# mcu.net
KiCad netlist of a schematic drawn in Altium Designer
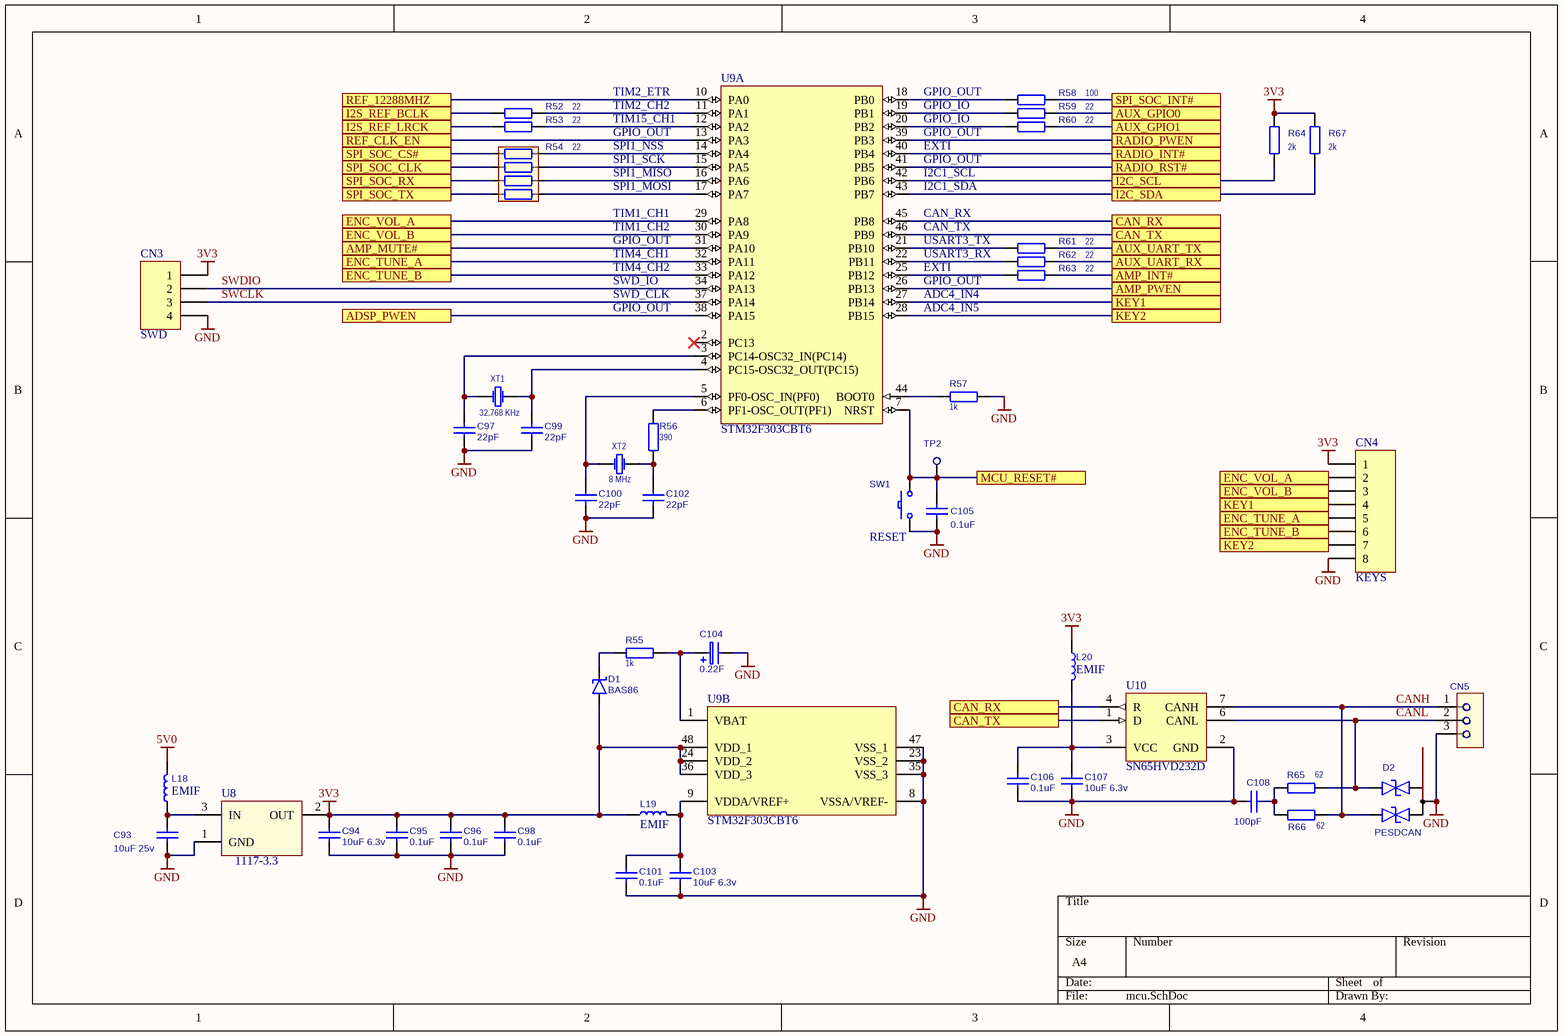
[diagram p0: mcu.SchDoc]

(export (version "E")
  (design (tool "Eeschema 10.0.6"))
  (components
    (comp (ref "C93")
      (value "10uF 25v")
      (footprint "C0805")
      (description "CAP_NPOL")
      (fields (field (name "Comment") "GRM21BR61E106KA73L"))
      (libsource (lib "capacitors") (part "CAP_NPOL"))
    )
    (comp (ref "C94")
      (value "10uF 6.3v")
      (footprint "Capacitors:C0603")
      (description "CAP_NPOL")
      (fields (field (name "Comment") "CC0603MRX5R5BB106"))
      (libsource (lib "capacitors") (part "CAP_NPOL"))
    )
    (comp (ref "C95")
      (value "0.1uF")
      (footprint "Capacitors:C0603")
      (description "CAP_NPOL")
      (fields (field (name "Comment") "CC0603KRX7R9BB104"))
      (libsource (lib "capacitors") (part "CAP_NPOL"))
    )
    (comp (ref "C96")
      (value "0.1uF")
      (footprint "Capacitors:C0603")
      (description "CAP_NPOL")
      (fields (field (name "Comment") "CC0603KRX7R9BB104"))
      (libsource (lib "capacitors") (part "CAP_NPOL"))
    )
    (comp (ref "C97")
      (value "22pF")
      (footprint "Capacitors:C0603")
      (description "CAP_NPOL")
      (fields (field (name "Comment") "CL10C220JB8NNNC"))
      (libsource (lib "capacitors") (part "CAP_NPOL"))
    )
    (comp (ref "C98")
      (value "0.1uF")
      (footprint "Capacitors:C0603")
      (description "CAP_NPOL")
      (fields (field (name "Comment") "CC0603KRX7R9BB104"))
      (libsource (lib "capacitors") (part "CAP_NPOL"))
    )
    (comp (ref "C99")
      (value "22pF")
      (footprint "Capacitors:C0603")
      (description "CAP_NPOL")
      (fields (field (name "Comment") "CL10C220JB8NNNC"))
      (libsource (lib "capacitors") (part "CAP_NPOL"))
    )
    (comp (ref "C100")
      (value "22pF")
      (footprint "Capacitors:C0603")
      (description "CAP_NPOL")
      (fields (field (name "Comment") "CL10C220JB8NNNC"))
      (libsource (lib "capacitors") (part "CAP_NPOL"))
    )
    (comp (ref "C101")
      (value "0.1uF")
      (footprint "Capacitors:C0603")
      (description "CAP_NPOL")
      (fields (field (name "Comment") "CC0603KRX7R9BB104"))
      (libsource (lib "capacitors") (part "CAP_NPOL"))
    )
    (comp (ref "C102")
      (value "22pF")
      (footprint "Capacitors:C0603")
      (description "CAP_NPOL")
      (fields (field (name "Comment") "CL10C220JB8NNNC"))
      (libsource (lib "capacitors") (part "CAP_NPOL"))
    )
    (comp (ref "C103")
      (value "10uF 6.3v")
      (footprint "Capacitors:C0603")
      (description "CAP_NPOL")
      (fields (field (name "Comment") "CC0603MRX5R5BB106"))
      (libsource (lib "capacitors") (part "CAP_NPOL"))
    )
    (comp (ref "C104")
      (value "0.22F")
      (footprint "DS/DSK")
      (description "CAP_POL")
      (libsource (lib "capacitors") (part "CAP_POL"))
    )
    (comp (ref "C105")
      (value "0.1uF")
      (footprint "Capacitors:C0603")
      (description "CAP_NPOL")
      (fields (field (name "Comment") "C1608X7R1H104K080AA"))
      (libsource (lib "capacitors") (part "CAP_NPOL"))
    )
    (comp (ref "C106")
      (value "0.1uF")
      (footprint "Capacitors:C0603")
      (description "CAP_NPOL")
      (fields (field (name "Comment") "CC0603KRX7R9BB104"))
      (libsource (lib "capacitors") (part "CAP_NPOL"))
    )
    (comp (ref "C107")
      (value "10uF 6.3v")
      (footprint "Capacitors:C0603")
      (description "CAP_NPOL")
      (fields (field (name "Comment") "CC0603MRX5R5BB106"))
      (libsource (lib "capacitors") (part "CAP_NPOL"))
    )
    (comp (ref "C108")
      (value "100pF")
      (footprint "Capacitors:C0603")
      (description "CAP_NPOL")
      (fields (field (name "Comment") "CC0603JRNPO9BN101"))
      (libsource (lib "capacitors") (part "CAP_NPOL"))
    )
    (comp (ref "CN3")
      (value "SWD")
      (footprint "PLS-4")
      (description "Header, 4-Pin")
      (fields (field (name "PUBLISHER") "Altium Limited"))
      (libsource (lib "HDR") (part "HDR 4"))
    )
    (comp (ref "CN4")
      (value "KEYS")
      (footprint "1.25-8AW")
      (description "Header, 8-Pin")
      (fields (field (name "PUBLISHER") "Altium Limited"))
      (libsource (lib "HDR") (part "HDR 8"))
    )
    (comp (ref "CN5")
      (value "DGxxx-3")
      (footprint "DG308-2.54-3P")
      (description "PCB terminal block")
      (libsource (lib "DGxxx") (part "DGxxx-3"))
    )
    (comp (ref "D1")
      (value "BAS86")
      (footprint "SOD-80C")
      (description "SHOTTKY")
      (libsource (lib "diodes") (part "SHOTTKY"))
    )
    (comp (ref "D2")
      (value "PESDCAN")
      (footprint "SOT-23-3")
      (description "TVS Diodes")
      (fields (field (name "Comment") "PESD"))
      (libsource (lib "diodes") (part "TVS_BIDIR_DUAL"))
    )
    (comp (ref "L18")
      (value "EMIF")
      (footprint "IND0603")
      (description "IND_WO_IRON")
      (fields (field (name "Comment") "BLM18AG102SN1D"))
      (libsource (lib "inductors") (part "IND_WO_IRON"))
    )
    (comp (ref "L19")
      (value "EMIF")
      (footprint "IND0603")
      (description "IND_WO_IRON")
      (fields (field (name "Comment") "BLM18AG102SN1D"))
      (libsource (lib "inductors") (part "IND_WO_IRON"))
    )
    (comp (ref "L20")
      (value "EMIF")
      (footprint "IND0603")
      (description "IND_WO_IRON")
      (fields (field (name "Comment") "BLM18AG102SN1D"))
      (libsource (lib "inductors") (part "IND_WO_IRON"))
    )
    (comp (ref "R52")
      (value "22")
      (footprint "R0603")
      (description "RES")
      (libsource (lib "resistors") (part "RESISTOR"))
    )
    (comp (ref "R53")
      (value "22")
      (footprint "R0603")
      (description "RES")
      (libsource (lib "resistors") (part "RESISTOR"))
    )
    (comp (ref "R54")
      (value "22")
      (footprint "Resistors:R0804X4")
      (description "ARRAY")
      (fields (field (name "Comment") "TC124-JR-0722RL"))
      (libsource (lib "resistors") (part "ARRAY"))
    )
    (comp (ref "R55")
      (value "1k")
      (footprint "R0603")
      (description "RES")
      (libsource (lib "resistors") (part "RESISTOR"))
    )
    (comp (ref "R56")
      (value "390")
      (footprint "R0603")
      (description "RES")
      (libsource (lib "resistors") (part "RESISTOR"))
    )
    (comp (ref "R57")
      (value "1k")
      (footprint "R0603")
      (description "RES")
      (fields (field (name "Comment") "0"))
      (libsource (lib "resistors") (part "RESISTOR"))
    )
    (comp (ref "R58")
      (value "100")
      (footprint "R0603")
      (description "RES")
      (libsource (lib "resistors") (part "RESISTOR"))
    )
    (comp (ref "R59")
      (value "22")
      (footprint "R0603")
      (description "RES")
      (libsource (lib "resistors") (part "RESISTOR"))
    )
    (comp (ref "R60")
      (value "22")
      (footprint "R0603")
      (description "RES")
      (libsource (lib "resistors") (part "RESISTOR"))
    )
    (comp (ref "R61")
      (value "22")
      (footprint "R0603")
      (description "RES")
      (libsource (lib "resistors") (part "RESISTOR"))
    )
    (comp (ref "R62")
      (value "22")
      (footprint "R0603")
      (description "RES")
      (libsource (lib "resistors") (part "RESISTOR"))
    )
    (comp (ref "R63")
      (value "22")
      (footprint "R0603")
      (description "RES")
      (libsource (lib "resistors") (part "RESISTOR"))
    )
    (comp (ref "R64")
      (value "2k")
      (footprint "R0603")
      (description "RES")
      (libsource (lib "resistors") (part "RESISTOR"))
    )
    (comp (ref "R65")
      (value "62")
      (footprint "R0603")
      (description "RES")
      (libsource (lib "resistors") (part "RESISTOR"))
    )
    (comp (ref "R66")
      (value "62")
      (footprint "R0603")
      (description "RES")
      (libsource (lib "resistors") (part "RESISTOR"))
    )
    (comp (ref "R67")
      (value "2k")
      (footprint "R0603")
      (description "RES")
      (libsource (lib "resistors") (part "RESISTOR"))
    )
    (comp (ref "SW1")
      (value "RESET")
      (footprint "TACTM-34N-F")
      (description "Microswitches, DTSMB-3 series")
      (libsource (lib "SW-TACT-2PIN") (part "SW tact 2-pin"))
    )
    (comp (ref "TP2")
      (value "TEST-POINT")
      (footprint "PAD")
      (description "PCB terminal block")
      (libsource (lib "TestPoint") (part "TEST-POINT"))
    )
    (comp (ref "U8")
      (value "1117-3.3")
      (footprint "SOT-223")
      (description "LM1117")
      (fields (field (name "Comment") "1117-xxx"))
      (libsource (lib "LM1117") (part "LM1117"))
    )
    (comp (ref "U9")
      (value "STM32F303CBT6")
      (footprint "STM-LQFP48_N")
      (libsource (lib "STMicroelectronics STM32 F3") (part "STM32F303CBT6"))
    )
    (comp (ref "U10")
      (value "SN65HVD232D")
      (footprint "SO-8:D008_N")
      (description "SN65HVD232")
      (libsource (lib "SN65HVD23x") (part "SN65HVD232"))
    )
    (comp (ref "XT1")
      (value "32.768 KHz")
      (footprint "DT38")
      (description "Xtal")
      (fields (field (name "Comment") "XTAL"))
      (libsource (lib "xtal") (part "XTAL"))
    )
    (comp (ref "XT2")
      (value "8 MHz")
      (footprint "xtal:HC-49/S-SMD")
      (description "Xtal")
      (fields (field (name "Comment") "XTAL"))
      (libsource (lib "xtal") (part "XTAL"))
    )
  )
  (nets
    (net (code "1") (name "/ADSP_PWEN") (class "Default")
      (node (ref "U9") (pin "38") (pinfunction "PA15_38") (pintype "bidirectional"))
    )
    (net (code "2") (name "/AMP_INT#") (class "Default")
      (node (ref "R63") (pin "1") (pinfunction "1_1") (pintype "passive"))
    )
    (net (code "3") (name "/AMP_MUTE#") (class "Default")
      (node (ref "U9") (pin "31") (pinfunction "PA10_31") (pintype "bidirectional"))
    )
    (net (code "4") (name "/AMP_PWEN") (class "Default")
      (node (ref "U9") (pin "26") (pinfunction "PB13_26") (pintype "bidirectional"))
    )
    (net (code "5") (name "/AUX_GPIO0") (class "Default")
      (node (ref "R59") (pin "1") (pinfunction "1_1") (pintype "passive"))
    )
    (net (code "6") (name "/AUX_GPIO1") (class "Default")
      (node (ref "R60") (pin "1") (pinfunction "1_1") (pintype "passive"))
    )
    (net (code "7") (name "/AUX_UART_RX") (class "Default")
      (node (ref "R62") (pin "1") (pinfunction "1_1") (pintype "passive"))
    )
    (net (code "8") (name "/AUX_UART_TX") (class "Default")
      (node (ref "R61") (pin "1") (pinfunction "1_1") (pintype "passive"))
    )
    (net (code "9") (name "/CANH") (class "Default")
      (node (ref "CN5") (pin "1") (pinfunction "1_1") (pintype "passive"))
      (node (ref "D2") (pin "1") (pinfunction "A_1") (pintype "passive"))
      (node (ref "R66") (pin "1") (pinfunction "1_1") (pintype "passive"))
      (node (ref "U10") (pin "7") (pinfunction "CANH_7") (pintype "passive"))
    )
    (net (code "10") (name "/CANL") (class "Default")
      (node (ref "CN5") (pin "2") (pinfunction "2_2") (pintype "passive"))
      (node (ref "D2") (pin "2") (pinfunction "B_2") (pintype "passive"))
      (node (ref "R65") (pin "1") (pinfunction "1_1") (pintype "passive"))
      (node (ref "U10") (pin "6") (pinfunction "CANL_6") (pintype "passive"))
    )
    (net (code "11") (name "/CAN_RX") (class "Default")
      (node (ref "U10") (pin "4") (pinfunction "R_4") (pintype "output"))
      (node (ref "U9") (pin "45") (pinfunction "PB8_45") (pintype "bidirectional"))
    )
    (net (code "12") (name "/CAN_TX") (class "Default")
      (node (ref "U10") (pin "1") (pinfunction "D_1") (pintype "input"))
      (node (ref "U9") (pin "46") (pinfunction "PB9_46") (pintype "bidirectional"))
    )
    (net (code "13") (name "/ENC_TUNE_A") (class "Default")
      (node (ref "CN4") (pin "5") (pinfunction "5_5") (pintype "passive"))
      (node (ref "U9") (pin "32") (pinfunction "PA11_32") (pintype "bidirectional"))
    )
    (net (code "14") (name "/ENC_TUNE_B") (class "Default")
      (node (ref "CN4") (pin "6") (pinfunction "6_6") (pintype "passive"))
      (node (ref "U9") (pin "33") (pinfunction "PA12_33") (pintype "bidirectional"))
    )
    (net (code "15") (name "/ENC_VOL_A") (class "Default")
      (node (ref "CN4") (pin "2") (pinfunction "2_2") (pintype "passive"))
      (node (ref "U9") (pin "29") (pinfunction "PA8_29") (pintype "bidirectional"))
    )
    (net (code "16") (name "/ENC_VOL_B") (class "Default")
      (node (ref "CN4") (pin "3") (pinfunction "3_3") (pintype "passive"))
      (node (ref "U9") (pin "30") (pinfunction "PA9_30") (pintype "bidirectional"))
    )
    (net (code "17") (name "/I2C_SCL") (class "Default")
      (node (ref "R64") (pin "1") (pinfunction "1_1") (pintype "passive"))
      (node (ref "U9") (pin "42") (pinfunction "PB6_42") (pintype "bidirectional"))
    )
    (net (code "18") (name "/I2C_SDA") (class "Default")
      (node (ref "R67") (pin "1") (pinfunction "1_1") (pintype "passive"))
      (node (ref "U9") (pin "43") (pinfunction "PB7_43") (pintype "bidirectional"))
    )
    (net (code "19") (name "/I2S_REF_BCLK") (class "Default")
      (node (ref "R52") (pin "2") (pinfunction "2_2") (pintype "passive"))
    )
    (net (code "20") (name "/I2S_REF_LRCK") (class "Default")
      (node (ref "R53") (pin "2") (pinfunction "2_2") (pintype "passive"))
    )
    (net (code "21") (name "/KEY1") (class "Default")
      (node (ref "CN4") (pin "4") (pinfunction "4_4") (pintype "passive"))
      (node (ref "U9") (pin "27") (pinfunction "PB14_27") (pintype "bidirectional"))
    )
    (net (code "22") (name "/KEY2") (class "Default")
      (node (ref "CN4") (pin "7") (pinfunction "7_7") (pintype "passive"))
      (node (ref "U9") (pin "28") (pinfunction "PB15_28") (pintype "bidirectional"))
    )
    (net (code "23") (name "/MCU_RESET#") (class "Default")
      (node (ref "C105") (pin "1") (pinfunction "1_1") (pintype "passive"))
      (node (ref "SW1") (pin "2") (pintype "passive"))
      (node (ref "TP2") (pin "1") (pinfunction "1_1") (pintype "passive"))
      (node (ref "U9") (pin "7") (pinfunction "NRST_7") (pintype "bidirectional"))
    )
    (net (code "24") (name "/RADIO_INT#") (class "Default")
      (node (ref "U9") (pin "40") (pinfunction "PB4_40") (pintype "bidirectional"))
    )
    (net (code "25") (name "/RADIO_PWEN") (class "Default")
      (node (ref "U9") (pin "39") (pinfunction "PB3_39") (pintype "bidirectional"))
    )
    (net (code "26") (name "/RADIO_RST#") (class "Default")
      (node (ref "U9") (pin "41") (pinfunction "PB5_41") (pintype "bidirectional"))
    )
    (net (code "27") (name "/REF_12288MHZ") (class "Default")
      (node (ref "U9") (pin "10") (pinfunction "PA0_10") (pintype "bidirectional"))
    )
    (net (code "28") (name "/REF_CLK_EN") (class "Default")
      (node (ref "U9") (pin "13") (pinfunction "PA3_13") (pintype "bidirectional"))
    )
    (net (code "29") (name "/SPI_SOC_CLK") (class "Default")
      (node (ref "R54") (pin "6") (pinfunction "6_6") (pintype "passive"))
    )
    (net (code "30") (name "/SPI_SOC_CS#") (class "Default")
      (node (ref "R54") (pin "8") (pinfunction "8_8") (pintype "passive"))
    )
    (net (code "31") (name "/SPI_SOC_INT#") (class "Default")
      (node (ref "R58") (pin "1") (pinfunction "1_1") (pintype "passive"))
    )
    (net (code "32") (name "/SPI_SOC_RX") (class "Default")
      (node (ref "R54") (pin "4") (pinfunction "4_4") (pintype "passive"))
    )
    (net (code "33") (name "/SPI_SOC_TX") (class "Default")
      (node (ref "R54") (pin "2") (pinfunction "2_2") (pintype "passive"))
    )
    (net (code "34") (name "/SWCLK") (class "Default")
      (node (ref "CN3") (pin "3") (pinfunction "3_3") (pintype "passive"))
      (node (ref "U9") (pin "37") (pinfunction "PA14_37") (pintype "bidirectional"))
    )
    (net (code "35") (name "/SWDIO") (class "Default")
      (node (ref "CN3") (pin "2") (pinfunction "2_2") (pintype "passive"))
      (node (ref "U9") (pin "34") (pinfunction "PA13_34") (pintype "bidirectional"))
    )
    (net (code "36") (name "3V3") (class "Default")
      (node (ref "C94") (pin "2") (pinfunction "2_2") (pintype "passive"))
      (node (ref "C95") (pin "1") (pinfunction "1_1") (pintype "passive"))
      (node (ref "C96") (pin "1") (pinfunction "1_1") (pintype "passive"))
      (node (ref "C98") (pin "1") (pinfunction "1_1") (pintype "passive"))
      (node (ref "CN3") (pin "1") (pinfunction "1_1") (pintype "passive"))
      (node (ref "CN4") (pin "1") (pinfunction "1_1") (pintype "passive"))
      (node (ref "D1") (pin "1") (pinfunction "A_1") (pintype "passive"))
      (node (ref "L19") (pin "2") (pintype "passive"))
      (node (ref "L20") (pin "2") (pintype "passive"))
      (node (ref "R64") (pin "2") (pinfunction "2_2") (pintype "passive"))
      (node (ref "R67") (pin "2") (pinfunction "2_2") (pintype "passive"))
      (node (ref "U8") (pin "2") (pinfunction "OUT_2") (pintype "passive"))
      (node (ref "U9") (pin "24") (pinfunction "VDD_2_24") (pintype "power_in"))
      (node (ref "U9") (pin "36") (pinfunction "VDD_3_36") (pintype "power_in"))
      (node (ref "U9") (pin "48") (pinfunction "VDD_1_48") (pintype "power_in"))
    )
    (net (code "37") (name "5V0") (class "Default") (node (ref "L18") (pin "1") (pintype "passive")))
    (net (code "38") (name "GND") (class "Default")
      (node (ref "C100") (pin "2") (pinfunction "2_2") (pintype "passive"))
      (node (ref "C101") (pin "2") (pinfunction "2_2") (pintype "passive"))
      (node (ref "C102") (pin "2") (pinfunction "2_2") (pintype "passive"))
      (node (ref "C103") (pin "2") (pinfunction "2_2") (pintype "passive"))
      (node (ref "C104") (pin "2") (pinfunction "-_2") (pintype "passive"))
      (node (ref "C105") (pin "2") (pinfunction "2_2") (pintype "passive"))
      (node (ref "C106") (pin "2") (pinfunction "2_2") (pintype "passive"))
      (node (ref "C107") (pin "2") (pinfunction "2_2") (pintype "passive"))
      (node (ref "C108") (pin "1") (pinfunction "1_1") (pintype "passive"))
      (node (ref "C93") (pin "1") (pinfunction "1_1") (pintype "passive"))
      (node (ref "C94") (pin "1") (pinfunction "1_1") (pintype "passive"))
      (node (ref "C95") (pin "2") (pinfunction "2_2") (pintype "passive"))
      (node (ref "C96") (pin "2") (pinfunction "2_2") (pintype "passive"))
      (node (ref "C97") (pin "2") (pinfunction "2_2") (pintype "passive"))
      (node (ref "C98") (pin "2") (pinfunction "2_2") (pintype "passive"))
      (node (ref "C99") (pin "2") (pinfunction "2_2") (pintype "passive"))
      (node (ref "CN3") (pin "4") (pinfunction "4_4") (pintype "passive"))
      (node (ref "CN4") (pin "8") (pinfunction "8_8") (pintype "passive"))
      (node (ref "CN5") (pin "3") (pinfunction "3_3") (pintype "passive"))
      (node (ref "D2") (pin "3") (pinfunction "C_3") (pintype "passive"))
      (node (ref "R57") (pin "2") (pinfunction "2_2") (pintype "passive"))
      (node (ref "SW1") (pin "1") (pintype "passive"))
      (node (ref "U10") (pin "2") (pinfunction "GND_2") (pintype "power_in"))
      (node (ref "U8") (pin "1") (pinfunction "GND_1") (pintype "passive"))
      (node (ref "U9") (pin "23") (pinfunction "VSS_2_23") (pintype "power_in"))
      (node (ref "U9") (pin "35") (pinfunction "VSS_3_35") (pintype "power_in"))
      (node (ref "U9") (pin "47") (pinfunction "VSS_1_47") (pintype "power_in"))
      (node (ref "U9") (pin "8") (pinfunction "VSSA/VREF-_8") (pintype "power_in"))
    )
    (net (code "39") (name "Net-(C102-Pad1)") (class "Default")
      (node (ref "C102") (pin "1") (pinfunction "1_1") (pintype "passive"))
      (node (ref "R56") (pin "2") (pinfunction "2_2") (pintype "passive"))
      (node (ref "XT2") (pin "2") (pintype "passive"))
    )
    (net (code "40") (name "Net-(C104-+)") (class "Default")
      (node (ref "C104") (pin "1") (pinfunction "+_1") (pintype "passive"))
      (node (ref "R55") (pin "1") (pinfunction "1_1") (pintype "passive"))
      (node (ref "U9") (pin "1") (pinfunction "VBAT_1") (pintype "power_in"))
    )
    (net (code "41") (name "Net-(C108-Pad2)") (class "Default")
      (node (ref "C108") (pin "2") (pinfunction "2_2") (pintype "passive"))
      (node (ref "R65") (pin "2") (pinfunction "2_2") (pintype "passive"))
      (node (ref "R66") (pin "2") (pinfunction "2_2") (pintype "passive"))
    )
    (net (code "42") (name "Net-(D1-K)") (class "Default")
      (node (ref "D1") (pin "2") (pinfunction "K_2") (pintype "passive"))
      (node (ref "R55") (pin "2") (pinfunction "2_2") (pintype "passive"))
    )
    (net (code "43") (name "Net-(U8-IN)") (class "Default")
      (node (ref "C93") (pin "2") (pinfunction "2_2") (pintype "passive"))
      (node (ref "L18") (pin "2") (pintype "passive"))
      (node (ref "U8") (pin "3") (pinfunction "IN_3") (pintype "passive"))
    )
    (net (code "44") (name "Net-(U9A-BOOT0)") (class "Default")
      (node (ref "R57") (pin "1") (pinfunction "1_1") (pintype "passive"))
      (node (ref "U9") (pin "44") (pinfunction "BOOT0_44") (pintype "input"))
    )
    (net (code "45") (name "Net-(U9A-PA1)") (class "Default")
      (node (ref "R52") (pin "1") (pinfunction "1_1") (pintype "passive"))
      (node (ref "U9") (pin "11") (pinfunction "PA1_11") (pintype "bidirectional"))
    )
    (net (code "46") (name "Net-(U9A-PA2)") (class "Default")
      (node (ref "R53") (pin "1") (pinfunction "1_1") (pintype "passive"))
      (node (ref "U9") (pin "12") (pinfunction "PA2_12") (pintype "bidirectional"))
    )
    (net (code "47") (name "Net-(U9A-PA4)") (class "Default")
      (node (ref "R54") (pin "7") (pinfunction "7_7") (pintype "passive"))
      (node (ref "U9") (pin "14") (pinfunction "PA4_14") (pintype "bidirectional"))
    )
    (net (code "48") (name "Net-(U9A-PA5)") (class "Default")
      (node (ref "R54") (pin "5") (pinfunction "5_5") (pintype "passive"))
      (node (ref "U9") (pin "15") (pinfunction "PA5_15") (pintype "bidirectional"))
    )
    (net (code "49") (name "Net-(U9A-PA6)") (class "Default")
      (node (ref "R54") (pin "3") (pinfunction "3_3") (pintype "passive"))
      (node (ref "U9") (pin "16") (pinfunction "PA6_16") (pintype "bidirectional"))
    )
    (net (code "50") (name "Net-(U9A-PA7)") (class "Default")
      (node (ref "R54") (pin "1") (pinfunction "1_1") (pintype "passive"))
      (node (ref "U9") (pin "17") (pinfunction "PA7_17") (pintype "bidirectional"))
    )
    (net (code "51") (name "Net-(U9A-PB0)") (class "Default")
      (node (ref "R58") (pin "2") (pinfunction "2_2") (pintype "passive"))
      (node (ref "U9") (pin "18") (pinfunction "PB0_18") (pintype "bidirectional"))
    )
    (net (code "52") (name "Net-(U9A-PB1)") (class "Default")
      (node (ref "R59") (pin "2") (pinfunction "2_2") (pintype "passive"))
      (node (ref "U9") (pin "19") (pinfunction "PB1_19") (pintype "bidirectional"))
    )
    (net (code "53") (name "Net-(U9A-PB2)") (class "Default")
      (node (ref "R60") (pin "2") (pinfunction "2_2") (pintype "passive"))
      (node (ref "U9") (pin "20") (pinfunction "PB2_20") (pintype "bidirectional"))
    )
    (net (code "54") (name "Net-(U9A-PB10)") (class "Default")
      (node (ref "R61") (pin "2") (pinfunction "2_2") (pintype "passive"))
      (node (ref "U9") (pin "21") (pinfunction "PB10_21") (pintype "bidirectional"))
    )
    (net (code "55") (name "Net-(U9A-PB11)") (class "Default")
      (node (ref "R62") (pin "2") (pinfunction "2_2") (pintype "passive"))
      (node (ref "U9") (pin "22") (pinfunction "PB11_22") (pintype "bidirectional"))
    )
    (net (code "56") (name "Net-(U9A-PB12)") (class "Default")
      (node (ref "R63") (pin "2") (pinfunction "2_2") (pintype "passive"))
      (node (ref "U9") (pin "25") (pinfunction "PB12_25") (pintype "bidirectional"))
    )
    (net (code "57") (name "Net-(U9A-PC14-OSC32_IN(PC14))") (class "Default")
      (node (ref "C97") (pin "1") (pinfunction "1_1") (pintype "passive"))
      (node (ref "U9") (pin "3") (pinfunction "PC14-OSC32_IN(PC14)_3") (pintype "bidirectional"))
      (node (ref "XT1") (pin "1") (pintype "passive"))
    )
    (net (code "58") (name "Net-(U9A-PC15-OSC32_OUT(PC15))") (class "Default")
      (node (ref "C99") (pin "1") (pinfunction "1_1") (pintype "passive"))
      (node (ref "U9") (pin "4") (pinfunction "PC15-OSC32_OUT(PC15)_4") (pintype "bidirectional"))
      (node (ref "XT1") (pin "2") (pintype "passive"))
    )
    (net (code "59") (name "Net-(U9A-PF0-OSC_IN(PF0))") (class "Default")
      (node (ref "C100") (pin "1") (pinfunction "1_1") (pintype "passive"))
      (node (ref "U9") (pin "5") (pinfunction "PF0-OSC_IN(PF0)_5") (pintype "bidirectional"))
      (node (ref "XT2") (pin "1") (pintype "passive"))
    )
    (net (code "60") (name "Net-(U9A-PF1-OSC_OUT(PF1))") (class "Default")
      (node (ref "R56") (pin "1") (pinfunction "1_1") (pintype "passive"))
      (node (ref "U9") (pin "6") (pinfunction "PF1-OSC_OUT(PF1)_6") (pintype "bidirectional"))
    )
    (net (code "61") (name "Net-(U9B-VDDA{slash}VREF+)") (class "Default")
      (node (ref "C101") (pin "1") (pinfunction "1_1") (pintype "passive"))
      (node (ref "C103") (pin "1") (pinfunction "1_1") (pintype "passive"))
      (node (ref "L19") (pin "1") (pintype "passive"))
      (node (ref "U9") (pin "9") (pinfunction "VDDA/VREF+_9") (pintype "power_in"))
    )
    (net (code "62") (name "Net-(U10-VCC)") (class "Default")
      (node (ref "C106") (pin "1") (pinfunction "1_1") (pintype "passive"))
      (node (ref "C107") (pin "1") (pinfunction "1_1") (pintype "passive"))
      (node (ref "L20") (pin "1") (pintype "passive"))
      (node (ref "U10") (pin "3") (pinfunction "VCC_3") (pintype "power_in"))
    )
    (net (code "63") (name "unconnected-(U9A-PC13-Pad2)") (class "Default")
      (node (ref "U9") (pin "2") (pinfunction "PC13_2") (pintype "bidirectional+no_connect"))
    )
  )
)
